# ESP-WROOM-02-BREAK.net
KiCad netlist of a schematic drawn in EAGLE
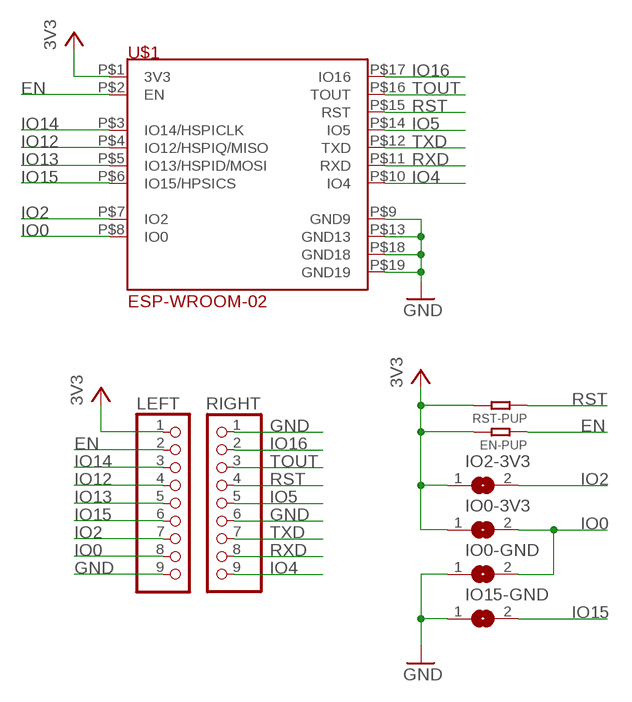
[diagram p0: schematic, sheet 1]

(export (version "E")
  (design (tool "Eeschema 10.0.6"))
  (components
    (comp (ref "EN-PUP")
      (value "10K")
      (footprint "eagle-import:R0805")
      (fields (field (name "MPN") "RC0805FR-0710KL"))
      (libsource (lib "eagle-import") (part "SMD-RES-10K-1%-1/8W(0805)"))
    )
    (comp (ref "IO0-3V3")
      (value "SJ")
      (footprint "eagle-import:SJ")
      (libsource (lib "eagle-import") (part "SJ"))
    )
    (comp (ref "IO0-GND")
      (value "SJ")
      (footprint "eagle-import:SJ")
      (libsource (lib "eagle-import") (part "SJ"))
    )
    (comp (ref "IO2-3V3")
      (value "SJ")
      (footprint "eagle-import:SJ")
      (libsource (lib "eagle-import") (part "SJ"))
    )
    (comp (ref "IO15-GND")
      (value "SJ")
      (footprint "eagle-import:SJ")
      (libsource (lib "eagle-import") (part "SJ"))
    )
    (comp (ref "LEFT")
      (value "PINHD-1X9")
      (footprint "eagle-import:1X09")
      (libsource (lib "eagle-import") (part "PINHD-1X9"))
    )
    (comp (ref "RIGHT")
      (value "PINHD-1X9")
      (footprint "eagle-import:1X09")
      (libsource (lib "eagle-import") (part "PINHD-1X9"))
    )
    (comp (ref "RST-PUP")
      (value "10K")
      (footprint "eagle-import:R0805")
      (fields (field (name "MPN") "RC0805FR-0710KL"))
      (libsource (lib "eagle-import") (part "SMD-RES-10K-1%-1/8W(0805)"))
    )
    (comp (ref "U$1")
      (value "ESP-WROOM-02")
      (footprint "eagle-import:ESP-WROOM-02")
      (libsource (lib "eagle-import") (part "ESP-WROOM-02"))
    )
  )
  (nets
    (net (code "1") (name "/EN") (class "Default")
      (node (ref "EN-PUP") (pin "1") (pinfunction "1_1") (pintype "passive"))
      (node (ref "LEFT") (pin "2") (pinfunction "2_2") (pintype "passive"))
      (node (ref "U$1") (pin "P$2") (pinfunction "EN_P$2") (pintype "bidirectional"))
    )
    (net (code "2") (name "/IO0") (class "Default")
      (node (ref "IO0-3V3") (pin "2") (pinfunction "2_2") (pintype "passive"))
      (node (ref "IO0-GND") (pin "2") (pinfunction "2_2") (pintype "passive"))
      (node (ref "LEFT") (pin "8") (pinfunction "8_8") (pintype "passive"))
      (node (ref "U$1") (pin "P$8") (pinfunction "IO0_P$8") (pintype "bidirectional"))
    )
    (net (code "3") (name "/IO2") (class "Default")
      (node (ref "IO2-3V3") (pin "2") (pinfunction "2_2") (pintype "passive"))
      (node (ref "LEFT") (pin "7") (pinfunction "7_7") (pintype "passive"))
      (node (ref "U$1") (pin "P$7") (pinfunction "IO2_P$7") (pintype "bidirectional"))
    )
    (net (code "4") (name "/IO4") (class "Default")
      (node (ref "RIGHT") (pin "9") (pinfunction "9_9") (pintype "passive"))
      (node (ref "U$1") (pin "P$10") (pinfunction "IO4_P$10") (pintype "bidirectional"))
    )
    (net (code "5") (name "/IO5") (class "Default")
      (node (ref "RIGHT") (pin "5") (pinfunction "5_5") (pintype "passive"))
      (node (ref "U$1") (pin "P$14") (pinfunction "IO5_P$14") (pintype "bidirectional"))
    )
    (net (code "6") (name "/IO12") (class "Default")
      (node (ref "LEFT") (pin "4") (pinfunction "4_4") (pintype "passive"))
      (node (ref "U$1") (pin "P$4") (pinfunction "IO12/HSPIQ/MISO_P$4") (pintype "bidirectional"))
    )
    (net (code "7") (name "/IO13") (class "Default")
      (node (ref "LEFT") (pin "5") (pinfunction "5_5") (pintype "passive"))
      (node (ref "U$1") (pin "P$5") (pinfunction "IO13/HSPID/MOSI_P$5") (pintype "bidirectional"))
    )
    (net (code "8") (name "/IO14") (class "Default")
      (node (ref "LEFT") (pin "3") (pinfunction "3_3") (pintype "passive"))
      (node (ref "U$1") (pin "P$3") (pinfunction "IO14/HSPICLK_P$3") (pintype "bidirectional"))
    )
    (net (code "9") (name "/IO15") (class "Default")
      (node (ref "IO15-GND") (pin "2") (pinfunction "2_2") (pintype "passive"))
      (node (ref "LEFT") (pin "6") (pinfunction "6_6") (pintype "passive"))
      (node (ref "U$1") (pin "P$6") (pinfunction "IO15/HPSICS_P$6") (pintype "bidirectional"))
    )
    (net (code "10") (name "/IO16") (class "Default")
      (node (ref "RIGHT") (pin "2") (pinfunction "2_2") (pintype "passive"))
      (node (ref "U$1") (pin "P$17") (pinfunction "IO16_P$17") (pintype "bidirectional"))
    )
    (net (code "11") (name "/RST") (class "Default")
      (node (ref "RIGHT") (pin "4") (pinfunction "4_4") (pintype "passive"))
      (node (ref "RST-PUP") (pin "1") (pinfunction "1_1") (pintype "passive"))
      (node (ref "U$1") (pin "P$15") (pinfunction "RST_P$15") (pintype "bidirectional"))
    )
    (net (code "12") (name "/RXD") (class "Default")
      (node (ref "RIGHT") (pin "8") (pinfunction "8_8") (pintype "passive"))
      (node (ref "U$1") (pin "P$11") (pinfunction "RXD_P$11") (pintype "bidirectional"))
    )
    (net (code "13") (name "/TOUT") (class "Default")
      (node (ref "RIGHT") (pin "3") (pinfunction "3_3") (pintype "passive"))
      (node (ref "U$1") (pin "P$16") (pinfunction "TOUT_P$16") (pintype "bidirectional"))
    )
    (net (code "14") (name "/TXD") (class "Default")
      (node (ref "RIGHT") (pin "7") (pinfunction "7_7") (pintype "passive"))
      (node (ref "U$1") (pin "P$12") (pinfunction "TXD_P$12") (pintype "bidirectional"))
    )
    (net (code "15") (name "3V3") (class "Default")
      (node (ref "EN-PUP") (pin "2") (pinfunction "2_2") (pintype "passive"))
      (node (ref "IO0-3V3") (pin "1") (pinfunction "1_1") (pintype "passive"))
      (node (ref "IO2-3V3") (pin "1") (pinfunction "1_1") (pintype "passive"))
      (node (ref "LEFT") (pin "1") (pinfunction "1_1") (pintype "passive"))
      (node (ref "RST-PUP") (pin "2") (pinfunction "2_2") (pintype "passive"))
      (node (ref "U$1") (pin "P$1") (pinfunction "3V3_P$1") (pintype "bidirectional"))
    )
    (net (code "16") (name "GND") (class "Default")
      (node (ref "IO0-GND") (pin "1") (pinfunction "1_1") (pintype "passive"))
      (node (ref "IO15-GND") (pin "1") (pinfunction "1_1") (pintype "passive"))
      (node (ref "LEFT") (pin "9") (pinfunction "9_9") (pintype "passive"))
      (node (ref "RIGHT") (pin "1") (pinfunction "1_1") (pintype "passive"))
      (node (ref "RIGHT") (pin "6") (pinfunction "6_6") (pintype "passive"))
      (node (ref "U$1") (pin "P$13") (pinfunction "GND13_P$13") (pintype "bidirectional"))
      (node (ref "U$1") (pin "P$18") (pinfunction "GND18_P$18") (pintype "bidirectional"))
      (node (ref "U$1") (pin "P$19") (pinfunction "GND19_P$19") (pintype "bidirectional"))
      (node (ref "U$1") (pin "P$9") (pinfunction "GND9_P$9") (pintype "bidirectional"))
    )
  )
)
